# 06-GPS.net
KiCad netlist of a schematic drawn in Altium Designer
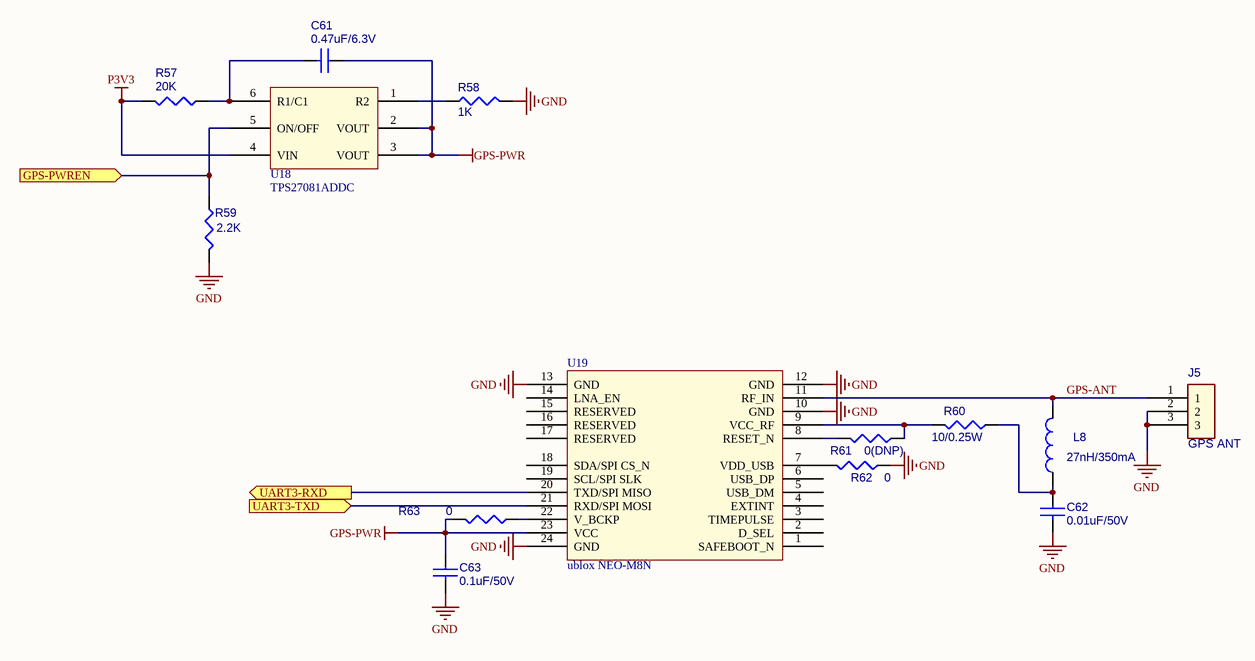
[diagram p0: 06-GPS.SchDoc]

(export (version "E")
  (design (tool "Eeschema 10.0.6"))
  (components
    (comp (ref "C61") (value "0.47uF/6.3V") (footprint "0402") (libsource (lib "*") (part "P_CAP NP")))
    (comp (ref "C62") (value "0.01uF/50V") (libsource (lib "*") (part "P_CAP NP")))
    (comp (ref "C63") (value "0.1uF/50V") (libsource (lib "*") (part "P_CAP NP")))
    (comp (ref "J5") (value "GPS ANT") (footprint "ANT") (libsource (lib "*") (part "HRS_U_0.FL-R-SMT-10")))
    (comp (ref "L8")
      (value "27nH/350mA")
      (footprint "0402")
      (libsource (lib "*") (part "2.2UH_LPS3015-222MLC_1.5A_20%~D"))
    )
    (comp (ref "R57") (value "20K") (footprint "0402") (libsource (lib "*") (part "P_R")))
    (comp (ref "R58") (value "1K") (footprint "0402") (libsource (lib "*") (part "P_R")))
    (comp (ref "R59") (value "2.2K") (footprint "0402") (libsource (lib "*") (part "P_R")))
    (comp (ref "R60") (value "10/0.25W") (footprint "1206") (libsource (lib "*") (part "P_R")))
    (comp (ref "R61") (value "0(DNP)") (footprint "0402") (libsource (lib "*") (part "P_R")))
    (comp (ref "R62") (value "0") (footprint "0402") (libsource (lib "*") (part "P_R")))
    (comp (ref "R63") (value "0") (footprint "0402") (libsource (lib "*") (part "P_R")))
    (comp (ref "U18")
      (value "TPS27081ADDC")
      (footprint "SOT23-6")
      (libsource (lib "Schlib") (part "TPS27081A"))
    )
    (comp (ref "U19") (value "ublox NEO-M8N") (footprint "NEO-6") (libsource (lib "Schlib") (part "NEO-M8")))
  )
  (nets
    (net (code "1") (name "/GPS-ANT") (class "Default")
      (node (ref "J5") (pin "1") (pinfunction "1_1") (pintype "passive"))
      (node (ref "L8") (pin "2") (pinfunction "2_2") (pintype "passive"))
      (node (ref "U19") (pin "11") (pinfunction "RF_IN_11") (pintype "passive"))
    )
    (net (code "2") (name "/GPS-PWREN") (class "Default")
      (node (ref "R59") (pin "2") (pinfunction "2_2") (pintype "passive"))
      (node (ref "U18") (pin "5") (pinfunction "ON/OFF_5") (pintype "passive"))
    )
    (net (code "3") (name "/UART3-RXD") (class "Default")
      (node (ref "U19") (pin "20") (pinfunction "TXD/SPI_MISO_20") (pintype "passive"))
    )
    (net (code "4") (name "/UART3-TXD") (class "Default")
      (node (ref "U19") (pin "21") (pinfunction "RXD/SPI_MOSI_21") (pintype "passive"))
    )
    (net (code "5") (name "GND") (class "Default")
      (node (ref "C62") (pin "2") (pinfunction "2_2") (pintype "passive"))
      (node (ref "C63") (pin "2") (pinfunction "2_2") (pintype "passive"))
      (node (ref "J5") (pin "2") (pinfunction "2_2") (pintype "passive"))
      (node (ref "J5") (pin "3") (pinfunction "3_3") (pintype "passive"))
      (node (ref "R58") (pin "1") (pinfunction "1_1") (pintype "passive"))
      (node (ref "R59") (pin "1") (pinfunction "1_1") (pintype "passive"))
      (node (ref "R62") (pin "1") (pinfunction "1_1") (pintype "passive"))
      (node (ref "U19") (pin "10") (pinfunction "GND_10") (pintype "passive"))
      (node (ref "U19") (pin "12") (pinfunction "GND_12") (pintype "passive"))
      (node (ref "U19") (pin "13") (pinfunction "GND_13") (pintype "passive"))
      (node (ref "U19") (pin "24") (pinfunction "GND_24") (pintype "passive"))
    )
    (net (code "6") (name "GPS-PWR") (class "Default")
      (node (ref "C61") (pin "1") (pinfunction "1_1") (pintype "passive"))
      (node (ref "C63") (pin "1") (pinfunction "1_1") (pintype "passive"))
      (node (ref "R63") (pin "2") (pinfunction "2_2") (pintype "passive"))
      (node (ref "U18") (pin "2") (pinfunction "VOUT_2") (pintype "passive"))
      (node (ref "U18") (pin "3") (pinfunction "VOUT_3") (pintype "passive"))
      (node (ref "U19") (pin "23") (pinfunction "VCC_23") (pintype "passive"))
    )
    (net (code "7") (name "Net-(C62-Pad1)") (class "Default")
      (node (ref "C62") (pin "1") (pinfunction "1_1") (pintype "passive"))
      (node (ref "L8") (pin "1") (pinfunction "1_1") (pintype "passive"))
      (node (ref "R60") (pin "1") (pinfunction "1_1") (pintype "passive"))
    )
    (net (code "8") (name "Net-(U18-R1{slash}C1)") (class "Default")
      (node (ref "C61") (pin "2") (pinfunction "2_2") (pintype "passive"))
      (node (ref "R57") (pin "2") (pinfunction "2_2") (pintype "passive"))
      (node (ref "U18") (pin "6") (pinfunction "R1/C1_6") (pintype "passive"))
    )
    (net (code "9") (name "Net-(U18-R2)") (class "Default")
      (node (ref "R58") (pin "2") (pinfunction "2_2") (pintype "passive"))
      (node (ref "U18") (pin "1") (pinfunction "R2_1") (pintype "passive"))
    )
    (net (code "10") (name "Net-(U19-RESET_N)") (class "Default")
      (node (ref "R61") (pin "2") (pinfunction "2_2") (pintype "passive"))
      (node (ref "U19") (pin "8") (pinfunction "RESET_N_8") (pintype "passive"))
    )
    (net (code "11") (name "Net-(U19-VCC_RF)") (class "Default")
      (node (ref "R60") (pin "2") (pinfunction "2_2") (pintype "passive"))
      (node (ref "R61") (pin "1") (pinfunction "1_1") (pintype "passive"))
      (node (ref "U19") (pin "9") (pinfunction "VCC_RF_9") (pintype "passive"))
    )
    (net (code "12") (name "Net-(U19-VDD_USB)") (class "Default")
      (node (ref "R62") (pin "2") (pinfunction "2_2") (pintype "passive"))
      (node (ref "U19") (pin "7") (pinfunction "VDD_USB_7") (pintype "passive"))
    )
    (net (code "13") (name "Net-(U19-V_BCKP)") (class "Default")
      (node (ref "R63") (pin "1") (pinfunction "1_1") (pintype "passive"))
      (node (ref "U19") (pin "22") (pinfunction "V_BCKP_22") (pintype "passive"))
    )
    (net (code "14") (name "P3V3") (class "Default")
      (node (ref "R57") (pin "1") (pinfunction "1_1") (pintype "passive"))
      (node (ref "U18") (pin "4") (pinfunction "VIN_4") (pintype "passive"))
    )
    (net (code "15") (name "unconnected-(U19-D_SEL-Pad2)") (class "Default")
      (node (ref "U19") (pin "2") (pinfunction "D_SEL_2") (pintype "passive"))
    )
    (net (code "16") (name "unconnected-(U19-EXTINT-Pad4)") (class "Default")
      (node (ref "U19") (pin "4") (pinfunction "EXTINT_4") (pintype "passive"))
    )
    (net (code "17") (name "unconnected-(U19-LNA_EN-Pad14)") (class "Default")
      (node (ref "U19") (pin "14") (pinfunction "LNA_EN_14") (pintype "passive"))
    )
    (net (code "18") (name "unconnected-(U19-RESERVED-Pad15)") (class "Default")
      (node (ref "U19") (pin "15") (pinfunction "RESERVED_15") (pintype "passive"))
    )
    (net (code "19") (name "unconnected-(U19-RESERVED-Pad16)") (class "Default")
      (node (ref "U19") (pin "16") (pinfunction "RESERVED_16") (pintype "passive"))
    )
    (net (code "20") (name "unconnected-(U19-RESERVED-Pad17)") (class "Default")
      (node (ref "U19") (pin "17") (pinfunction "RESERVED_17") (pintype "passive"))
    )
    (net (code "21") (name "unconnected-(U19-SAFEBOOT_N-Pad1)") (class "Default")
      (node (ref "U19") (pin "1") (pinfunction "SAFEBOOT_N_1") (pintype "passive"))
    )
    (net (code "22") (name "unconnected-(U19-SCL{slash}SPI_SLK-Pad19)") (class "Default")
      (node (ref "U19") (pin "19") (pinfunction "SCL/SPI_SLK_19") (pintype "passive"))
    )
    (net (code "23") (name "unconnected-(U19-SDA{slash}SPI_CS_N-Pad18)") (class "Default")
      (node (ref "U19") (pin "18") (pinfunction "SDA/SPI_CS_N_18") (pintype "passive"))
    )
    (net (code "24") (name "unconnected-(U19-TIMEPULSE-Pad3)") (class "Default")
      (node (ref "U19") (pin "3") (pinfunction "TIMEPULSE_3") (pintype "passive"))
    )
    (net (code "25") (name "unconnected-(U19-USB_DM-Pad5)") (class "Default")
      (node (ref "U19") (pin "5") (pinfunction "USB_DM_5") (pintype "passive"))
    )
    (net (code "26") (name "unconnected-(U19-USB_DP-Pad6)") (class "Default")
      (node (ref "U19") (pin "6") (pinfunction "USB_DP_6") (pintype "passive"))
    )
  )
)
